# SRX.net
KiCad netlist of a schematic drawn in Altium Designer
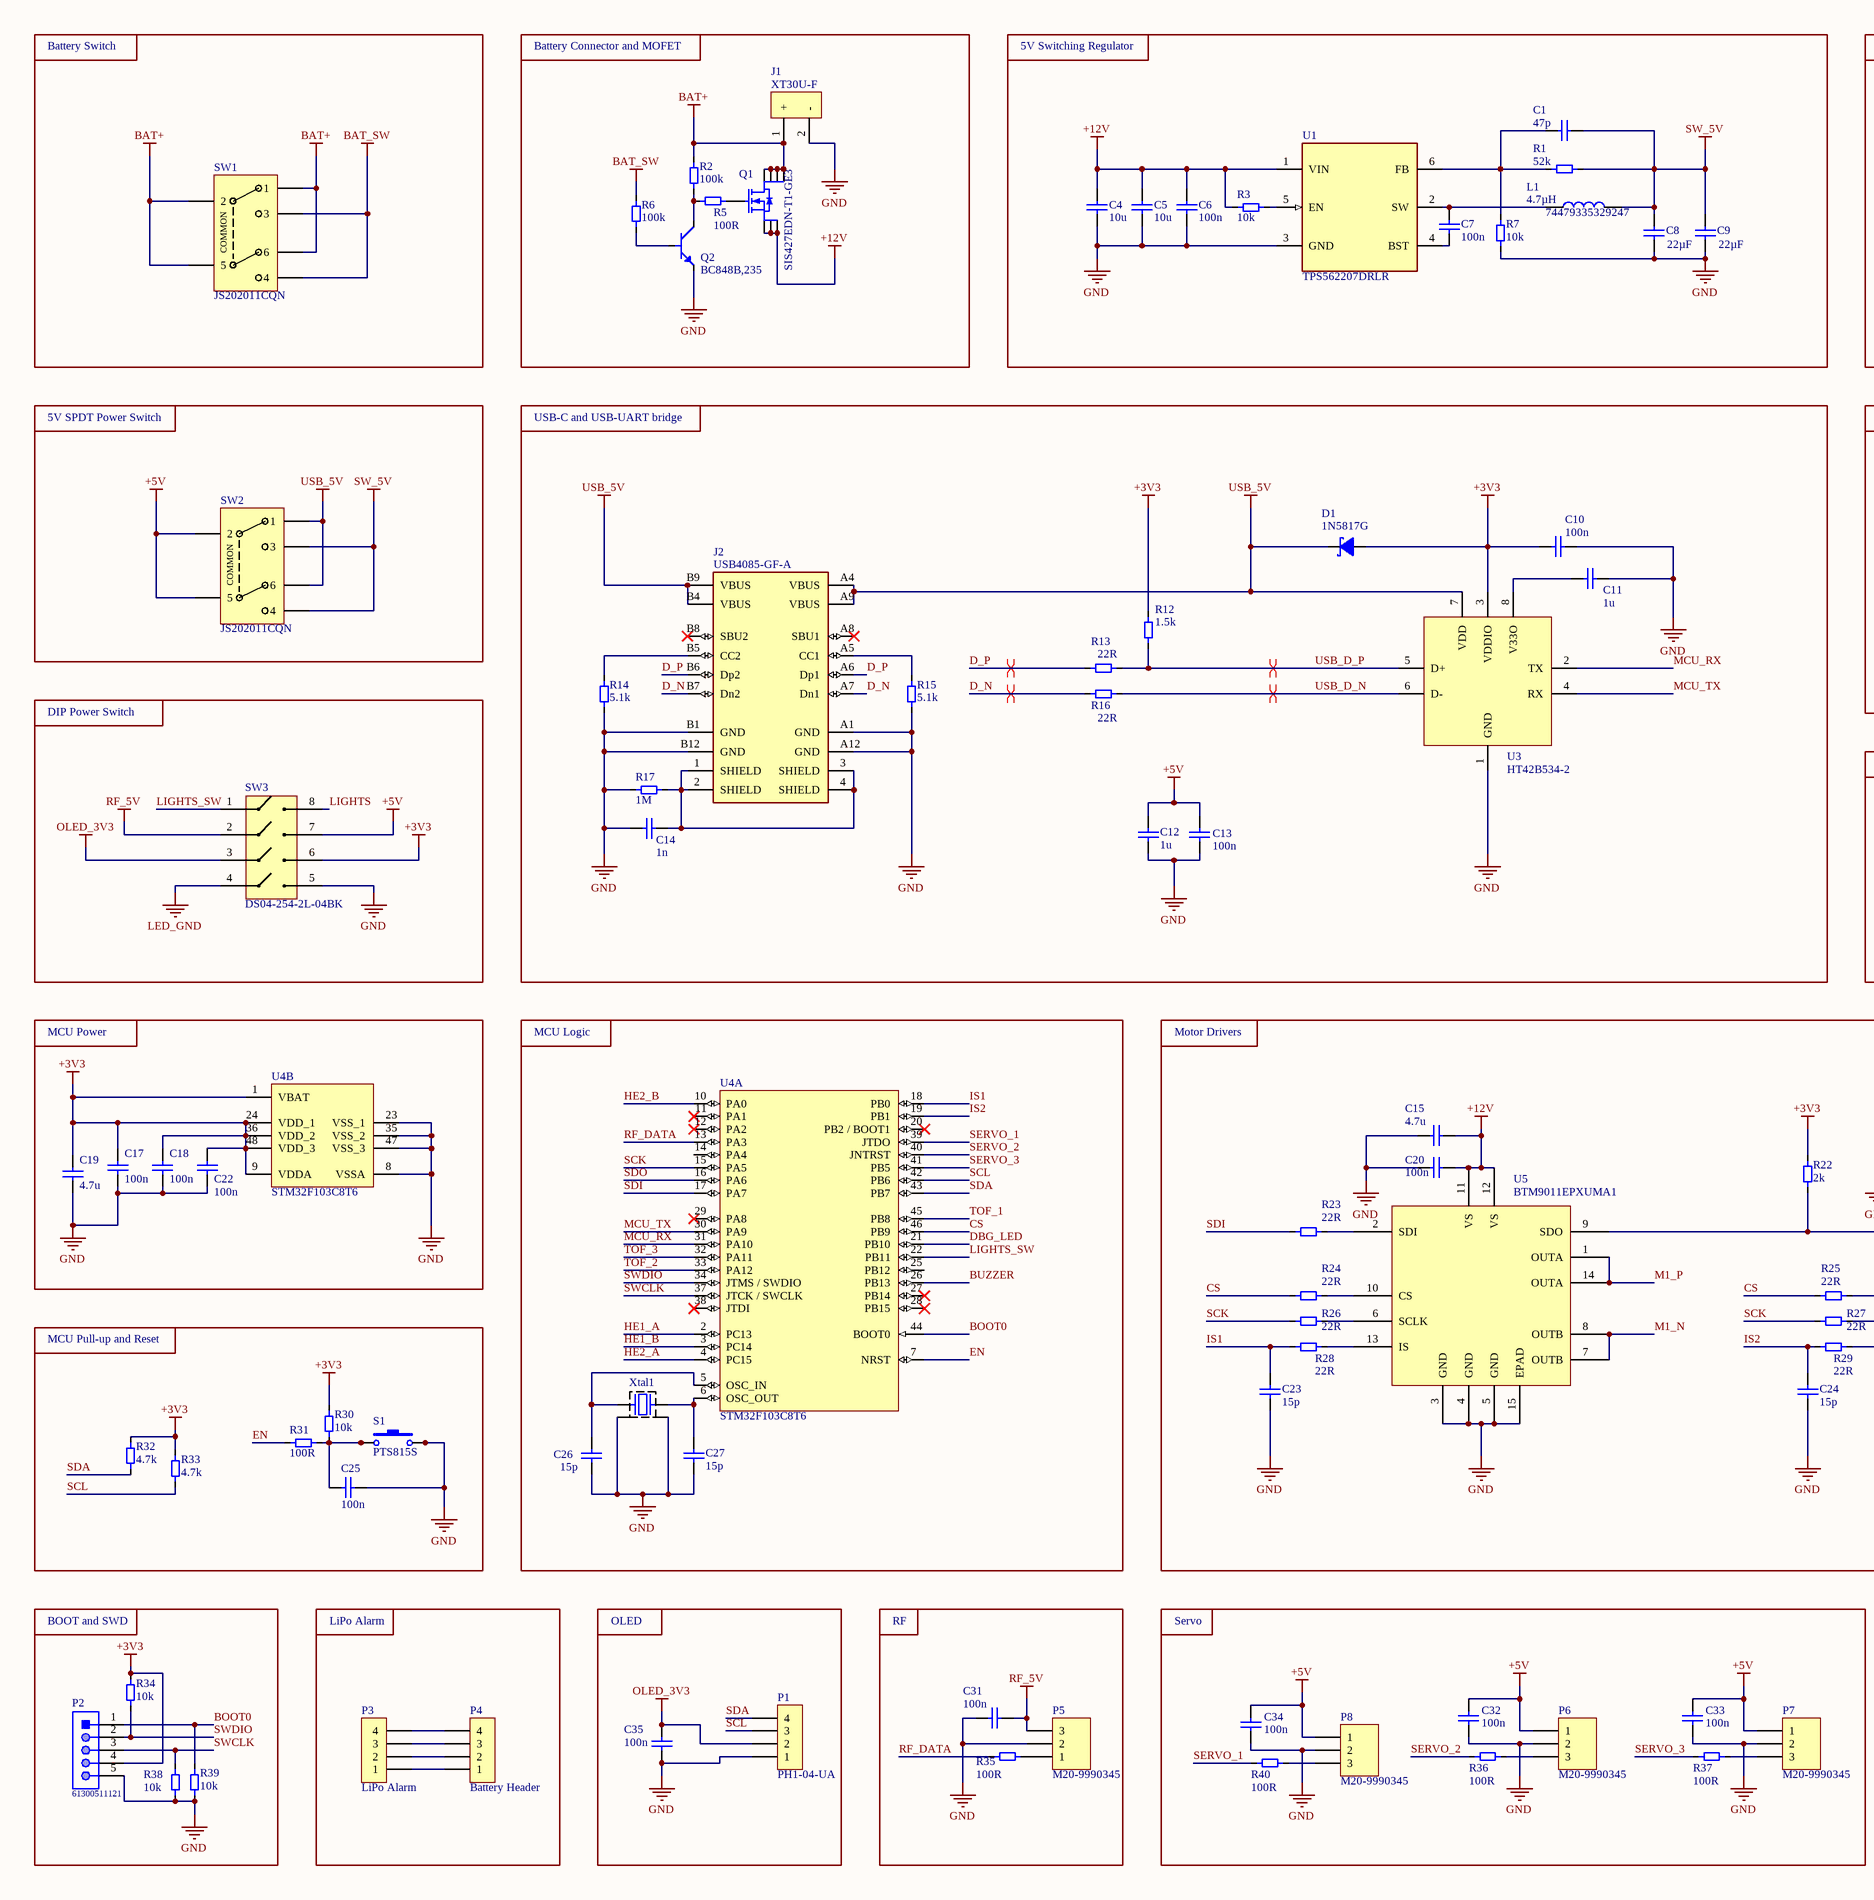
[diagram p0: SRX.SchDoc, left]
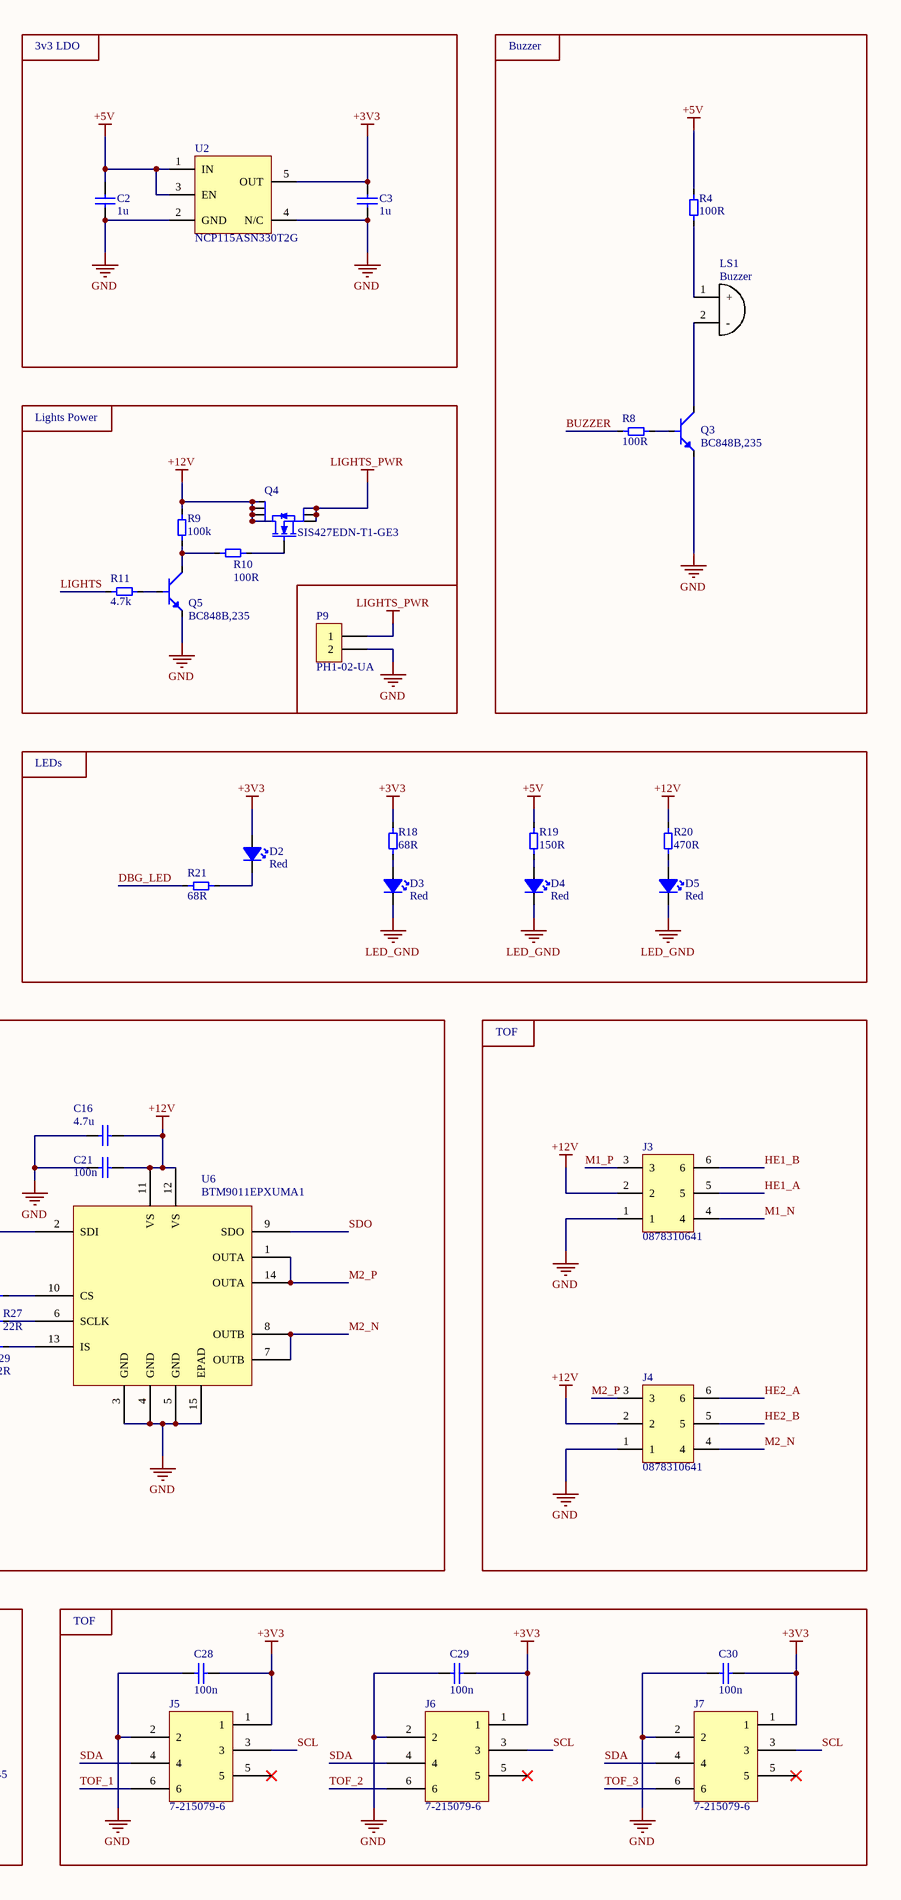
[diagram p1: SRX.SchDoc, right]

(export (version "E")
  (design (tool "Eeschema 10.0.6"))
  (components
    (comp (ref "C1")
      (value "47p")
      (footprint "MLCC_0603_M")
      (description "MLCC, 0603, 47p, 10%, 50V, X7R")
      (fields (field (name "MANUFACTURER") "Any") (field (name "TOLERANCE") "10%"))
      (libsource (lib "Krakul Vault") (part "CAPACITOR_NONPOL_IEC"))
    )
    (comp (ref "C2")
      (value "1u")
      (footprint "MLCC_0603_M")
      (description "MLCC, 0603, 1u, 10%, 50V, X5R")
      (fields (field (name "MANUFACTURER") "Any") (field (name "VOLTAGE") "50V"))
      (libsource (lib "Krakul Vault") (part "CAPACITOR_NONPOL_IEC"))
    )
    (comp (ref "C3")
      (value "1u")
      (footprint "MLCC_0603_M")
      (description "MLCC, 0603, 1u, 10%, 50V, X5R")
      (fields (field (name "MANUFACTURER") "Any") (field (name "VOLTAGE") "50V"))
      (libsource (lib "Krakul Vault") (part "CAPACITOR_NONPOL_IEC"))
    )
    (comp (ref "C4")
      (value "10u")
      (footprint "MLCC_0805_M")
      (description "MLCC, 0805, 10u, 10%, 50V, X5R")
      (fields (field (name "TOLERANCE") "10%") (field (name "VOLTAGE") "50V"))
      (libsource (lib "Krakul Vault") (part "CAPACITOR_NONPOL_IEC"))
    )
    (comp (ref "C5")
      (value "10u")
      (footprint "MLCC_0805_M")
      (description "MLCC, 0805, 10u, 10%, 50V, X5R")
      (fields (field (name "TOLERANCE") "10%") (field (name "VOLTAGE") "50V"))
      (libsource (lib "Krakul Vault") (part "CAPACITOR_NONPOL_IEC"))
    )
    (comp (ref "C6")
      (value "100n")
      (footprint "MLCC_0603_M")
      (description "MLCC, 0603, 100n, 10%, 50V, X7R")
      (fields (field (name "VOLTAGE") "50V") (field (name "TOLERANCE") "10%"))
      (libsource (lib "Krakul Vault") (part "CAPACITOR_NONPOL_IEC"))
    )
    (comp (ref "C7")
      (value "100n")
      (footprint "MLCC_0603_M")
      (description "MLCC, 0603, 100n, 10%, 50V, X7R")
      (fields (field (name "VOLTAGE") "50V") (field (name "TOLERANCE") "10%"))
      (libsource (lib "Krakul Vault") (part "CAPACITOR_NONPOL_IEC"))
    )
    (comp (ref "C8")
      (value "22µF")
      (footprint "1210_MLCC")
      (description "Capacitor;  Ceramic;  22uF;  Tol+10%;  SMT HighCapacitance;  16V;  X5R;  TR")
      (fields (field (name "TOLERANCE") "10%") (field (name "PART NUMBER") "Any"))
      (libsource (lib "Krakul Vault") (part "CAPACITOR_NONPOL_IEC"))
    )
    (comp (ref "C9")
      (value "22µF")
      (footprint "1210_MLCC")
      (description "Capacitor;  Ceramic;  22uF;  Tol+10%;  SMT HighCapacitance;  16V;  X5R;  TR")
      (fields (field (name "TOLERANCE") "10%") (field (name "PART NUMBER") "Any"))
      (libsource (lib "Krakul Vault") (part "CAPACITOR_NONPOL_IEC"))
    )
    (comp (ref "C10")
      (value "100n")
      (footprint "MLCC_0603_M")
      (description "MLCC, 0603, 100n, 10%, 50V, X7R")
      (fields (field (name "VOLTAGE") "50V") (field (name "TOLERANCE") "10%"))
      (libsource (lib "Krakul Vault") (part "CAPACITOR_NONPOL_IEC"))
    )
    (comp (ref "C11")
      (value "1u")
      (footprint "MLCC_0603_M")
      (description "MLCC, 0603, 1u, 10%, 50V, X5R")
      (fields (field (name "MANUFACTURER") "Any") (field (name "VOLTAGE") "50V"))
      (libsource (lib "Krakul Vault") (part "CAPACITOR_NONPOL_IEC"))
    )
    (comp (ref "C12")
      (value "1u")
      (footprint "MLCC_0603_M")
      (description "MLCC, 0603, 1u, 10%, 50V, X5R")
      (fields (field (name "MANUFACTURER") "Any") (field (name "VOLTAGE") "50V"))
      (libsource (lib "Krakul Vault") (part "CAPACITOR_NONPOL_IEC"))
    )
    (comp (ref "C13")
      (value "100n")
      (footprint "MLCC_0603_M")
      (description "MLCC, 0603, 100n, 10%, 50V, X7R")
      (fields (field (name "VOLTAGE") "50V") (field (name "TOLERANCE") "10%"))
      (libsource (lib "Krakul Vault") (part "CAPACITOR_NONPOL_IEC"))
    )
    (comp (ref "C14")
      (value "1n")
      (footprint "MLCC_0603_M")
      (description "MLCC, 0603, 1n, 10%, 50V, X5R")
      (fields (field (name "MANUFACTURER") "Any") (field (name "TOLERANCE") "10%"))
      (libsource (lib "Krakul Vault") (part "CAPACITOR_NONPOL_IEC"))
    )
    (comp (ref "C15")
      (value "4.7u")
      (footprint "MLCC_0603_M")
      (description "MLCC, 0603, 4.7u, 10%, 35V, X5R")
      (fields (field (name "TOLERANCE") "10%") (field (name "VOLTAGE") "35V"))
      (libsource (lib "Krakul Vault") (part "CAPACITOR_NONPOL_IEC"))
    )
    (comp (ref "C16")
      (value "4.7u")
      (footprint "MLCC_0603_M")
      (description "MLCC, 0603, 4.7u, 10%, 35V, X5R")
      (fields (field (name "TOLERANCE") "10%") (field (name "VOLTAGE") "35V"))
      (libsource (lib "Krakul Vault") (part "CAPACITOR_NONPOL_IEC"))
    )
    (comp (ref "C17")
      (value "100n")
      (footprint "MLCC_0603_M")
      (description "MLCC, 0603, 100n, 10%, 50V, X7R")
      (fields (field (name "VOLTAGE") "50V") (field (name "TOLERANCE") "10%"))
      (libsource (lib "Krakul Vault") (part "CAPACITOR_NONPOL_IEC"))
    )
    (comp (ref "C18")
      (value "100n")
      (footprint "MLCC_0603_M")
      (description "MLCC, 0603, 100n, 10%, 50V, X7R")
      (fields (field (name "VOLTAGE") "50V") (field (name "TOLERANCE") "10%"))
      (libsource (lib "Krakul Vault") (part "CAPACITOR_NONPOL_IEC"))
    )
    (comp (ref "C19")
      (value "4.7u")
      (footprint "MLCC_0805_M")
      (description "MLCC, 0805, 4.7u, 20%, 50V, X5R")
      (fields (field (name "MANUFACTURER") "Any") (field (name "VOLTAGE") "50V"))
      (libsource (lib "Krakul Vault") (part "CAPACITOR_NONPOL_IEC"))
    )
    (comp (ref "C20")
      (value "100n")
      (footprint "MLCC_0603_M")
      (description "MLCC, 0603, 100n, 10%, 35V, X7R")
      (fields (field (name "MANUFACTURER") "Any") (field (name "VOLTAGE") "35V"))
      (libsource (lib "Krakul Vault") (part "CAPACITOR_NONPOL_IEC"))
    )
    (comp (ref "C21")
      (value "100n")
      (footprint "MLCC_0603_M")
      (description "MLCC, 0603, 100n, 10%, 35V, X7R")
      (fields (field (name "MANUFACTURER") "Any") (field (name "VOLTAGE") "35V"))
      (libsource (lib "Krakul Vault") (part "CAPACITOR_NONPOL_IEC"))
    )
    (comp (ref "C22")
      (value "100n")
      (footprint "MLCC_0603_M")
      (description "MLCC, 0603, 100n, 10%, 50V, X7R")
      (fields (field (name "VOLTAGE") "50V") (field (name "TOLERANCE") "10%"))
      (libsource (lib "Krakul Vault") (part "CAPACITOR_NONPOL_IEC"))
    )
    (comp (ref "C23")
      (value "15p")
      (footprint "MLCC_0603_M")
      (description "MLCC, 0603, 15p, 5%, 50V, C0G/NP0")
      (fields (field (name "MANUFACTURER") "Any") (field (name "VOLTAGE") "50V"))
      (libsource (lib "Krakul Vault") (part "CAPACITOR_NONPOL_IEC"))
    )
    (comp (ref "C24")
      (value "15p")
      (footprint "MLCC_0603_M")
      (description "MLCC, 0603, 15p, 5%, 50V, C0G/NP0")
      (fields (field (name "MANUFACTURER") "Any") (field (name "VOLTAGE") "50V"))
      (libsource (lib "Krakul Vault") (part "CAPACITOR_NONPOL_IEC"))
    )
    (comp (ref "C25")
      (value "100n")
      (footprint "MLCC_0603_M")
      (description "MLCC, 0603, 100n, 10%, 50V, X7R")
      (fields (field (name "VOLTAGE") "50V") (field (name "TOLERANCE") "10%"))
      (libsource (lib "Krakul Vault") (part "CAPACITOR_NONPOL_IEC"))
    )
    (comp (ref "C26")
      (value "15p")
      (footprint "MLCC_0402_M")
      (description "MLCC, 0402, 15p, 10%, 25V, C0G/NP0")
      (fields (field (name "MANUFACTURER") "Any") (field (name "TOLERANCE") "10%"))
      (libsource (lib "Krakul Vault") (part "CAPACITOR_NONPOL_IEC"))
    )
    (comp (ref "C27")
      (value "15p")
      (footprint "MLCC_0402_M")
      (description "MLCC, 0402, 15p, 10%, 25V, C0G/NP0")
      (fields (field (name "MANUFACTURER") "Any") (field (name "TOLERANCE") "10%"))
      (libsource (lib "Krakul Vault") (part "CAPACITOR_NONPOL_IEC"))
    )
    (comp (ref "C28")
      (value "100n")
      (footprint "MLCC_0603_M")
      (description "MLCC, 0603, 100n, 10%, 50V, X7R")
      (fields (field (name "VOLTAGE") "50V") (field (name "TOLERANCE") "10%"))
      (libsource (lib "Krakul Vault") (part "CAPACITOR_NONPOL_IEC"))
    )
    (comp (ref "C29")
      (value "100n")
      (footprint "MLCC_0603_M")
      (description "MLCC, 0603, 100n, 10%, 50V, X7R")
      (fields (field (name "VOLTAGE") "50V") (field (name "TOLERANCE") "10%"))
      (libsource (lib "Krakul Vault") (part "CAPACITOR_NONPOL_IEC"))
    )
    (comp (ref "C30")
      (value "100n")
      (footprint "MLCC_0603_M")
      (description "MLCC, 0603, 100n, 10%, 50V, X7R")
      (fields (field (name "VOLTAGE") "50V") (field (name "TOLERANCE") "10%"))
      (libsource (lib "Krakul Vault") (part "CAPACITOR_NONPOL_IEC"))
    )
    (comp (ref "C31")
      (value "100n")
      (footprint "MLCC_0603_M")
      (description "MLCC, 0603, 100n, 10%, 50V, X7R")
      (fields (field (name "VOLTAGE") "50V") (field (name "TOLERANCE") "10%"))
      (libsource (lib "Krakul Vault") (part "CAPACITOR_NONPOL_IEC"))
    )
    (comp (ref "C32")
      (value "100n")
      (footprint "MLCC_0603_M")
      (description "MLCC, 0603, 100n, 10%, 50V, X7R")
      (fields (field (name "VOLTAGE") "50V") (field (name "TOLERANCE") "10%"))
      (libsource (lib "Krakul Vault") (part "CAPACITOR_NONPOL_IEC"))
    )
    (comp (ref "C33")
      (value "100n")
      (footprint "MLCC_0603_M")
      (description "MLCC, 0603, 100n, 10%, 50V, X7R")
      (fields (field (name "VOLTAGE") "50V") (field (name "TOLERANCE") "10%"))
      (libsource (lib "Krakul Vault") (part "CAPACITOR_NONPOL_IEC"))
    )
    (comp (ref "C34")
      (value "100n")
      (footprint "MLCC_0603_M")
      (description "MLCC, 0603, 100n, 10%, 50V, X7R")
      (fields (field (name "VOLTAGE") "50V") (field (name "TOLERANCE") "10%"))
      (libsource (lib "Krakul Vault") (part "CAPACITOR_NONPOL_IEC"))
    )
    (comp (ref "C35")
      (value "100n")
      (footprint "MLCC_0603_M")
      (description "MLCC, 0603, 100n, 10%, 50V, X7R")
      (fields (field (name "VOLTAGE") "50V") (field (name "TOLERANCE") "10%"))
      (libsource (lib "Krakul Vault") (part "CAPACITOR_NONPOL_IEC"))
    )
    (comp (ref "D1")
      (value "1N5817G")
      (footprint "SOD-323 based on 1N5817WS")
      (description "Rectifier Diode, Schottky, 1 Phase, 1 Element, 1A, 20V V(RRM), Silicon, DO-204AL")
      (fields (field (name "MANUFACTURER") "TWGMC / onsemi") (field (name "PART NUMBER") "1N5817WS"))
      (libsource (lib "Krakul Vault") (part "Schottky generic 2 pins"))
    )
    (comp (ref "D2")
      (value "Red")
      (footprint "0603 RED LED")
      (description "Generic red 0603 LED")
      (fields (field (name "PART NUMBER") "Any Red 0603 LED") (field (name "MANUFACTURER") "Any"))
      (libsource (lib "Krakul Vault") (part "LED generic"))
    )
    (comp (ref "D3")
      (value "Red")
      (footprint "0603 RED LED")
      (description "Generic red 0603 LED")
      (fields (field (name "PART NUMBER") "Any Red 0603 LED") (field (name "MANUFACTURER") "Any"))
      (libsource (lib "Krakul Vault") (part "LED generic"))
    )
    (comp (ref "D4")
      (value "Red")
      (footprint "0603 RED LED")
      (description "Generic red 0603 LED")
      (fields (field (name "PART NUMBER") "Any Red 0603 LED") (field (name "MANUFACTURER") "Any"))
      (libsource (lib "Krakul Vault") (part "LED generic"))
    )
    (comp (ref "D5")
      (value "Red")
      (footprint "0603 RED LED")
      (description "Generic red 0603 LED")
      (fields (field (name "PART NUMBER") "Any Red 0603 LED") (field (name "MANUFACTURER") "Any"))
      (libsource (lib "Krakul Vault") (part "LED generic"))
    )
    (comp (ref "J1")
      (value "XT30U-F")
      (footprint "XT30U-F")
      (description "Power Connector")
      (fields (field (name "MANUFACTURER") "AMASS"))
      (libsource (lib "Krakul Vault") (part "XT30U-F-Symbol-1"))
    )
    (comp (ref "J2")
      (value "USB4085-GF-A")
      (footprint "FP-USB4085-GF-A-MFG")
      (description "USB Connector, 16 Contact(s), Female, Right Angle, Solder Terminal, Locking, Receptacle")
      (fields (field (name "MANUFACTURER") "GCT") (field (name "PART NUMBER") "USB4800-03-A"))
      (libsource (lib "Krakul Vault") (part "USB4085-GF-A"))
    )
    (comp (ref "J3")
      (value "0878310641")
      (footprint "0878310641")
      (description "Conn Shrouded Header (2 Sides) HDR 6 POS 2mm Solder ST Top Entry Thru-Hole Milli-Grid Tube")
      (fields (field (name "MANUFACTURER") "Molex"))
      (libsource (lib "Krakul Vault") (part "0878310641"))
    )
    (comp (ref "J4")
      (value "0878310641")
      (footprint "0878310641")
      (description "Conn Shrouded Header (2 Sides) HDR 6 POS 2mm Solder ST Top Entry Thru-Hole Milli-Grid Tube")
      (fields (field (name "MANUFACTURER") "Molex"))
      (libsource (lib "Krakul Vault") (part "0878310641"))
    )
    (comp (ref "J5")
      (value "7-215079-6")
      (footprint "7-215079-6-Footprint-1")
      (description "Conn FFC Connector F 6 POS 1.27mm Solder ST Thru-Hole Automotive Box/Carton")
      (fields (field (name "MANUFACTURER") "TE Connectivity"))
      (libsource (lib "Krakul Vault") (part "7-215079-6"))
    )
    (comp (ref "J6")
      (value "7-215079-6")
      (footprint "7-215079-6-Footprint-1")
      (description "Conn FFC Connector F 6 POS 1.27mm Solder ST Thru-Hole Automotive Box/Carton")
      (fields (field (name "MANUFACTURER") "TE Connectivity"))
      (libsource (lib "Krakul Vault") (part "7-215079-6"))
    )
    (comp (ref "J7")
      (value "7-215079-6")
      (footprint "7-215079-6-Footprint-1")
      (description "Conn FFC Connector F 6 POS 1.27mm Solder ST Thru-Hole Automotive Box/Carton")
      (fields (field (name "MANUFACTURER") "TE Connectivity"))
      (libsource (lib "Krakul Vault") (part "7-215079-6"))
    )
    (comp (ref "L1")
      (value "74479335329247")
      (footprint "WE-PMFI_353220")
      (description "Power Inductor, 4.7Uh, 3.85A, Shielded Rohs Compliant: Yes")
      (fields (field (name "MANUFACTURER") "Wurth Elektronik") (field (name "ALTIUM_VALUE") "4.7µH"))
      (libsource (lib "Krakul Vault") (part "INDUCTOR_UNSHIELDED"))
    )
    (comp (ref "LS1")
      (value "Buzzer")
      (footprint "Buzzer-Footprint-1")
      (description "7mm")
      (fields (field (name "MANUFACTURER") "Unknown"))
      (libsource (lib "Krakul Vault") (part "Buzzer"))
    )
    (comp (ref "P1")
      (value "PH1-04-UA")
      (footprint "4Pos Pin Header Vertical")
      (description "4 POS 2.54mm Vertical THT Header")
      (fields (field (name "MANUFACTURER") "Adam Tech"))
      (libsource (lib "") (part "4POS GENERIC_1"))
    )
    (comp (ref "P2")
      (value "61300511121")
      (footprint "61300511121")
      (description "Conn Unshrouded Header HDR 5 POS 2.54mm Solder ST Top Entry Thru-Hole Bag")
      (fields (field (name "MANUFACTURER") "Wurth"))
      (libsource (lib "Krakul Vault") (part "WE-CN-1P-M-R5"))
    )
    (comp (ref "P3")
      (value "LiPo Alarm")
      (footprint "4Pos Pin Header Vertical")
      (description "4 POS 2.54mm Vertical THT Header")
      (fields (field (name "PART NUMBER") "PH1-04-UA") (field (name "MANUFACTURER") "Adam Tech"))
      (libsource (lib "Krakul Vault") (part "4POS GENERIC"))
    )
    (comp (ref "P4")
      (value "Battery Header")
      (footprint "4Pos Pin Header Vertical")
      (description "4 POS 2.54mm Vertical THT Header")
      (fields (field (name "PART NUMBER") "PH1-04-UA") (field (name "MANUFACTURER") "Adam Tech"))
      (libsource (lib "") (part "4POS GENERIC_1"))
    )
    (comp (ref "P5")
      (value "M20-9990345")
      (footprint "3Pos Pin Header")
      (description "Connector Header Through Hole 3 position 0.100\" (2.54mm)")
      (fields (field (name "MANUFACTURER") "Harwin Inc."))
      (libsource (lib "") (part "3 pin header_1"))
    )
    (comp (ref "P6")
      (value "M20-9990345")
      (footprint "3Pos Pin Header")
      (description "Connector Header Through Hole 3 position 0.100\" (2.54mm)")
      (fields (field (name "MANUFACTURER") "Harwin Inc."))
      (libsource (lib "Krakul Vault") (part "3 pin header"))
    )
    (comp (ref "P7")
      (value "M20-9990345")
      (footprint "3Pos Pin Header")
      (description "Connector Header Through Hole 3 position 0.100\" (2.54mm)")
      (fields (field (name "MANUFACTURER") "Harwin Inc."))
      (libsource (lib "Krakul Vault") (part "3 pin header"))
    )
    (comp (ref "P8")
      (value "M20-9990345")
      (footprint "3Pos Pin Header")
      (description "Connector Header Through Hole 3 position 0.100\" (2.54mm)")
      (fields (field (name "MANUFACTURER") "Harwin Inc."))
      (libsource (lib "Krakul Vault") (part "3 pin header"))
    )
    (comp (ref "P9")
      (value "PH1-02-UA")
      (footprint "2Pos Pin Header Vertical")
      (description "Conn Unshrouded Header HDR 2 POS 2.54mm Solder ST Top Entry Thru-Hole Bag")
      (fields (field (name "PART NUMBER") "PH1-04-UA") (field (name "MANUFACTURER") "Adam Tech"))
      (libsource (lib "Krakul Vault") (part "2POS GENERIC"))
    )
    (comp (ref "Q1")
      (value "SIS427EDN-T1-GE3")
      (footprint "Copy of TPN2R304PL,L1Q-Footprint-1")
      (description "Trans MOSFET P-CH 30V 15A 8-Pin PowerPAK EP T/R")
      (fields (field (name "MANUFACTURER") "Vishay Siliconix"))
      (libsource (lib "Krakul Vault") (part "P-CH MOSFET 8-pin v2"))
    )
    (comp (ref "Q2")
      (value "BC848B,235")
      (footprint "SOT-23-3")
      (description "Small Signal Bipolar Transistor, 0.1A I(C), 30V V(BR)CEO, 1-Element, NPN, Silicon, TO-236AB")
      (fields (field (name "MANUFACTURER") "Nexperia"))
      (libsource (lib "Krakul Vault") (part "NPN SOT23"))
    )
    (comp (ref "Q3")
      (value "BC848B,235")
      (footprint "SOT-23-3")
      (description "Small Signal Bipolar Transistor, 0.1A I(C), 30V V(BR)CEO, 1-Element, NPN, Silicon, TO-236AB")
      (fields (field (name "MANUFACTURER") "Nexperia"))
      (libsource (lib "Krakul Vault") (part "NPN SOT23"))
    )
    (comp (ref "Q4")
      (value "SIS427EDN-T1-GE3")
      (footprint "Copy of TPN2R304PL,L1Q-Footprint-1")
      (description "Trans MOSFET P-CH 30V 15A 8-Pin PowerPAK EP T/R")
      (fields (field (name "MANUFACTURER") "Vishay Siliconix"))
      (libsource (lib "Krakul Vault") (part "P-CH MOSFET 8-pin v2"))
    )
    (comp (ref "Q5")
      (value "BC848B,235")
      (footprint "SOT-23-3")
      (description "Small Signal Bipolar Transistor, 0.1A I(C), 30V V(BR)CEO, 1-Element, NPN, Silicon, TO-236AB")
      (fields (field (name "MANUFACTURER") "Nexperia"))
      (libsource (lib "Krakul Vault") (part "NPN SOT23"))
    )
    (comp (ref "R1")
      (value "52k")
      (footprint "Resistor_0603_M")
      (description "Resistor, 0603, 53.6k, 1%, 1/10W")
      (fields (field (name "MANUFACTURER") "Any") (field (name "TOLERANCE") "1%"))
      (libsource (lib "Krakul Vault") (part "RESISTOR_GENERIC_IEC"))
    )
    (comp (ref "R2")
      (value "100k")
      (footprint "Resistor_0603_M")
      (description "Resistor, 0603, 100k, 1%, 1/10W")
      (fields (field (name "TOLERANCE") "1%") (field (name "MANUFACTURER") "Any"))
      (libsource (lib "Krakul Vault") (part "RESISTOR_GENERIC_IEC"))
    )
    (comp (ref "R3")
      (value "10k")
      (footprint "Resistor_0603_M")
      (description "Resistor, 0603, 10k, 1%, 1/10W")
      (fields (field (name "MANUFACTURER") "Any") (field (name "TOLERANCE") "1%"))
      (libsource (lib "Krakul Vault") (part "RESISTOR_GENERIC_IEC"))
    )
    (comp (ref "R4")
      (value "100R")
      (footprint "Resistor_0603_M")
      (description "Resistor, 0603, 100R, 1%, 1/10W")
      (fields (field (name "POWER") "100mW") (field (name "MANUFACTURER") "Any"))
      (libsource (lib "Krakul Vault") (part "RESISTOR_GENERIC_IEC"))
    )
    (comp (ref "R5")
      (value "100R")
      (footprint "Resistor_0603_M")
      (description "Resistor, 0603, 100R, 1%, 1/10W")
      (fields (field (name "POWER") "100mW") (field (name "MANUFACTURER") "Any"))
      (libsource (lib "Krakul Vault") (part "RESISTOR_GENERIC_IEC"))
    )
    (comp (ref "R6")
      (value "100k")
      (footprint "Resistor_0603_M")
      (description "Resistor, 0603, 100k, 1%, 1/10W")
      (fields (field (name "TOLERANCE") "1%") (field (name "MANUFACTURER") "Any"))
      (libsource (lib "Krakul Vault") (part "RESISTOR_GENERIC_IEC"))
    )
    (comp (ref "R7")
      (value "10k")
      (footprint "Resistor_0603_M")
      (description "Resistor, 0603, 10k, 1%, 1/10W")
      (fields (field (name "MANUFACTURER") "Any") (field (name "TOLERANCE") "1%"))
      (libsource (lib "Krakul Vault") (part "RESISTOR_GENERIC_IEC"))
    )
    (comp (ref "R8")
      (value "100R")
      (footprint "Resistor_0603_M")
      (description "Resistor, 0603, 100R, 1%, 1/10W")
      (fields (field (name "POWER") "100mW") (field (name "MANUFACTURER") "Any"))
      (libsource (lib "Krakul Vault") (part "RESISTOR_GENERIC_IEC"))
    )
    (comp (ref "R9")
      (value "100k")
      (footprint "Resistor_0603_M")
      (description "Resistor, 0603, 100k, 1%, 1/10W")
      (fields (field (name "TOLERANCE") "1%") (field (name "MANUFACTURER") "Any"))
      (libsource (lib "Krakul Vault") (part "RESISTOR_GENERIC_IEC"))
    )
    (comp (ref "R10")
      (value "100R")
      (footprint "Resistor_0603_M")
      (description "Resistor, 0603, 100R, 1%, 1/10W")
      (fields (field (name "POWER") "100mW") (field (name "MANUFACTURER") "Any"))
      (libsource (lib "Krakul Vault") (part "RESISTOR_GENERIC_IEC"))
    )
    (comp (ref "R11")
      (value "4.7k")
      (footprint "Resistor_0603_M")
      (description "Resistor, 0603, 4.7k, 1%, 1/10W")
      (fields (field (name "MANUFACTURER") "Any") (field (name "POWER") "100mW"))
      (libsource (lib "Krakul Vault") (part "RESISTOR_GENERIC_IEC"))
    )
    (comp (ref "R12")
      (value "1.5k")
      (footprint "Resistor_0603_M")
      (description "Resistor, 0603, 1.5k, 1%, 1/10W")
      (fields (field (name "MANUFACTURER") "Any") (field (name "POWER") "100mW"))
      (libsource (lib "Krakul Vault") (part "RESISTOR_GENERIC_IEC"))
    )
    (comp (ref "R13")
      (value "22R")
      (footprint "Resistor_0603_M")
      (description "Resistor, 0603, 22R, 1%, 1/10W")
      (fields (field (name "TOLERANCE") "1%") (field (name "MANUFACTURER") "Any"))
      (libsource (lib "Krakul Vault") (part "RESISTOR_GENERIC_IEC"))
    )
    (comp (ref "R14")
      (value "5.1k")
      (footprint "Resistor_0603_M")
      (description "Resistor, 0603, 5.1k, 1%, 1/10W")
      (fields (field (name "POWER") "100mW") (field (name "MANUFACTURER") "Any"))
      (libsource (lib "Krakul Vault") (part "RESISTOR_GENERIC_IEC"))
    )
    (comp (ref "R15")
      (value "5.1k")
      (footprint "Resistor_0603_M")
      (description "Resistor, 0603, 5.1k, 1%, 1/10W")
      (fields (field (name "POWER") "100mW") (field (name "MANUFACTURER") "Any"))
      (libsource (lib "Krakul Vault") (part "RESISTOR_GENERIC_IEC"))
    )
    (comp (ref "R16")
      (value "22R")
      (footprint "Resistor_0603_M")
      (description "Resistor, 0603, 22R, 1%, 1/10W")
      (fields (field (name "TOLERANCE") "1%") (field (name "MANUFACTURER") "Any"))
      (libsource (lib "Krakul Vault") (part "RESISTOR_GENERIC_IEC"))
    )
    (comp (ref "R17")
      (value "1M")
      (footprint "Resistor_1206_M")
      (description "Resistor, 1206, 1M, 1%, 1/4W")
      (fields (field (name "MANUFACTURER") "Any"))
      (libsource (lib "Krakul Vault") (part "RESISTOR_GENERIC_IEC"))
    )
    (comp (ref "R18")
      (value "68R")
      (footprint "Resistor_0603_M")
      (description "Resistor, 0603, 100R, ≤5%, ≥1/16W")
      (fields (field (name "MANUFACTURER") "Any"))
      (libsource (lib "Krakul Vault") (part "RESISTOR_GENERIC_IEC"))
    )
    (comp (ref "R19")
      (value "150R")
      (footprint "Resistor_0603_M")
      (description "Resistor, 0603, 200R, 1%, 1/10W")
      (fields (field (name "TOLERANCE") "1%") (field (name "POWER") "100mW"))
      (libsource (lib "Krakul Vault") (part "RESISTOR_GENERIC_IEC"))
    )
    (comp (ref "R20")
      (value "470R")
      (footprint "Resistor_0603_M")
      (description "Resistor, 0603, 680R, 1%, 1/10W")
      (fields (field (name "POWER") "100mW") (field (name "TOLERANCE") "1%"))
      (libsource (lib "Krakul Vault") (part "RESISTOR_GENERIC_IEC"))
    )
    (comp (ref "R21")
      (value "68R")
      (footprint "Resistor_0603_M")
      (description "Resistor, 0603, 200R, 1%, 1/10W")
      (fields (field (name "TOLERANCE") "1%") (field (name "POWER") "100mW"))
      (libsource (lib "Krakul Vault") (part "RESISTOR_GENERIC_IEC"))
    )
    (comp (ref "R22")
      (value "2k")
      (footprint "Resistor_0603_M")
      (description "Resistor, 0603, 2k, 1%, 1/10W")
      (fields (field (name "MANUFACTURER") "Any") (field (name "POWER") "100mW"))
      (libsource (lib "Krakul Vault") (part "RESISTOR_GENERIC_IEC"))
    )
    (comp (ref "R23")
      (value "22R")
      (footprint "Resistor_0603_M")
      (description "Resistor, 0603, 22R, 1%, 1/10W")
      (fields (field (name "TOLERANCE") "1%") (field (name "MANUFACTURER") "Any"))
      (libsource (lib "Krakul Vault") (part "RESISTOR_GENERIC_IEC"))
    )
    (comp (ref "R24")
      (value "22R")
      (footprint "Resistor_0603_M")
      (description "Resistor, 0603, 22R, 1%, 1/10W")
      (fields (field (name "TOLERANCE") "1%") (field (name "MANUFACTURER") "Any"))
      (libsource (lib "Krakul Vault") (part "RESISTOR_GENERIC_IEC"))
    )
    (comp (ref "R25")
      (value "22R")
      (footprint "Resistor_0603_M")
      (description "Resistor, 0603, 22R, 1%, 1/10W")
      (fields (field (name "TOLERANCE") "1%") (field (name "MANUFACTURER") "Any"))
      (libsource (lib "Krakul Vault") (part "RESISTOR_GENERIC_IEC"))
    )
    (comp (ref "R26")
      (value "22R")
      (footprint "Resistor_0603_M")
      (description "Resistor, 0603, 22R, 1%, 1/10W")
      (fields (field (name "TOLERANCE") "1%") (field (name "MANUFACTURER") "Any"))
      (libsource (lib "Krakul Vault") (part "RESISTOR_GENERIC_IEC"))
    )
    (comp (ref "R27")
      (value "22R")
      (footprint "Resistor_0603_M")
      (description "Resistor, 0603, 22R, 1%, 1/10W")
      (fields (field (name "TOLERANCE") "1%") (field (name "MANUFACTURER") "Any"))
      (libsource (lib "Krakul Vault") (part "RESISTOR_GENERIC_IEC"))
    )
    (comp (ref "R28")
      (value "22R")
      (footprint "Resistor_0603_M")
      (description "Resistor, 0603, 22R, 1%, 1/10W")
      (fields (field (name "TOLERANCE") "1%") (field (name "MANUFACTURER") "Any"))
      (libsource (lib "Krakul Vault") (part "RESISTOR_GENERIC_IEC"))
    )
    (comp (ref "R29")
      (value "22R")
      (footprint "Resistor_0603_M")
      (description "Resistor, 0603, 22R, 1%, 1/10W")
      (fields (field (name "TOLERANCE") "1%") (field (name "MANUFACTURER") "Any"))
      (libsource (lib "Krakul Vault") (part "RESISTOR_GENERIC_IEC"))
    )
    (comp (ref "R30")
      (value "10k")
      (footprint "Resistor_0603_M")
      (description "Resistor, 0603, 10k, 1%, 1/10W")
      (fields (field (name "MANUFACTURER") "Any") (field (name "TOLERANCE") "1%"))
      (libsource (lib "Krakul Vault") (part "RESISTOR_GENERIC_IEC"))
    )
    (comp (ref "R31")
      (value "100R")
      (footprint "Resistor_0603_M")
      (description "Resistor, 0603, 100R, 1%, 1/10W")
      (fields (field (name "POWER") "100mW") (field (name "MANUFACTURER") "Any"))
      (libsource (lib "Krakul Vault") (part "RESISTOR_GENERIC_IEC"))
    )
    (comp (ref "R32")
      (value "4.7k")
      (footprint "Resistor_0603_M")
      (description "Resistor, 0603, 4.7k, 1%, 1/10W")
      (fields (field (name "MANUFACTURER") "Any") (field (name "POWER") "100mW"))
      (libsource (lib "Krakul Vault") (part "RESISTOR_GENERIC_IEC"))
    )
    (comp (ref "R33")
      (value "4.7k")
      (footprint "Resistor_0603_M")
      (description "Resistor, 0603, 4.7k, 1%, 1/10W")
      (fields (field (name "MANUFACTURER") "Any") (field (name "POWER") "100mW"))
      (libsource (lib "Krakul Vault") (part "RESISTOR_GENERIC_IEC"))
    )
    (comp (ref "R34")
      (value "10k")
      (footprint "Resistor_0603_M")
      (description "Resistor, 0603, 10k, 1%, 1/10W")
      (fields (field (name "MANUFACTURER") "Any") (field (name "TOLERANCE") "1%"))
      (libsource (lib "Krakul Vault") (part "RESISTOR_GENERIC_IEC"))
    )
    (comp (ref "R35")
      (value "100R")
      (footprint "Resistor_0603_M")
      (description "Resistor, 0603, 100R, 1%, 1/10W")
      (fields (field (name "POWER") "100mW") (field (name "MANUFACTURER") "Any"))
      (libsource (lib "Krakul Vault") (part "RESISTOR_GENERIC_IEC"))
    )
    (comp (ref "R36")
      (value "100R")
      (footprint "Resistor_0603_M")
      (description "Resistor, 0603, 100R, 1%, 1/10W")
      (fields (field (name "POWER") "100mW") (field (name "MANUFACTURER") "Any"))
      (libsource (lib "Krakul Vault") (part "RESISTOR_GENERIC_IEC"))
    )
    (comp (ref "R37")
      (value "100R")
      (footprint "Resistor_0603_M")
      (description "Resistor, 0603, 100R, 1%, 1/10W")
      (fields (field (name "POWER") "100mW") (field (name "MANUFACTURER") "Any"))
      (libsource (lib "Krakul Vault") (part "RESISTOR_GENERIC_IEC"))
    )
    (comp (ref "R38")
      (value "10k")
      (footprint "Resistor_0603_M")
      (description "Resistor, 0603, 10k, 1%, 1/10W")
      (fields (field (name "MANUFACTURER") "Any") (field (name "TOLERANCE") "1%"))
      (libsource (lib "Krakul Vault") (part "RESISTOR_GENERIC_IEC"))
    )
    (comp (ref "R39")
      (value "10k")
      (footprint "Resistor_0603_M")
      (description "Resistor, 0603, 10k, ≤5%, ≥1/16W")
      (fields (field (name "MANUFACTURER") "Any"))
      (libsource (lib "Krakul Vault") (part "RESISTOR_GENERIC_IEC"))
    )
    (comp (ref "R40")
      (value "100R")
      (footprint "Resistor_0603_M")
      (description "Resistor, 0603, 100R, 1%, 1/10W")
      (fields (field (name "POWER") "100mW") (field (name "MANUFACTURER") "Any"))
      (libsource (lib "Krakul Vault") (part "RESISTOR_GENERIC_IEC"))
    )
    (comp (ref "S1")
      (value "PTS815S")
      (footprint "PTS815 SJM 250 SMTR LFS")
      (description "Tactile Switches SWITCH TACTILE")
      (fields (field (name "MANUFACTURER") "C&K") (field (name "PART NUMBER") "PTS815 SJM 250 SMTR LFS"))
      (libsource (lib "Krakul Vault") (part "PTS815SJM250SMTRLFS"))
    )
    (comp (ref "SW1")
      (value "JS202011CQN")
      (footprint "FP-JS202011CQN-MFG")
      (description "Slide Switch, 1 Positions, Dpdt, Latched, 0.3A, 6Vdc, 6 Pcb Hole Cnt, Solder Terminal, Through")
      (fields (field (name "MANUFACTURER") "C&K"))
      (libsource (lib "Krakul Vault") (part "JS202011CQN-Symbol-1"))
    )
    (comp (ref "SW2")
      (value "JS202011CQN")
      (footprint "FP-JS202011CQN-MFG")
      (description "Slide Switch, 1 Positions, Dpdt, Latched, 0.3A, 6Vdc, 6 Pcb Hole Cnt, Solder Terminal, Through")
      (fields (field (name "MANUFACTURER") "C&K"))
      (libsource (lib "Krakul Vault") (part "JS202011CQN-Symbol-1"))
    )
    (comp (ref "SW3")
      (value "DS04-254-2L-04BK")
      (footprint "DS04-254-2L-04BK-Footprint-1")
      (description "Switch DIP OFF ON SPST 4 Flat Slide 0.025A 24VDC PC Pins 2.54mm Thru-Hole Tube")
      (fields (field (name "MANUFACTURER") "Same Sky"))
      (libsource (lib "Krakul Vault") (part "4 DIP switch"))
    )
    (comp (ref "U1")
      (value "TPS562207DRLR")
      (footprint "FP-DRL0006A-MFG")
      (description "4.3-V to 17-V input, 2-A synchronous buck converter in SOT563 6-SOT-5X3 -40 to 125")
      (fields (field (name "MANUFACTURER") "Texas Instruments"))
      (libsource (lib "Krakul Vault") (part "TPS562207DRLR"))
    )
    (comp (ref "U2")
      (value "NCP115ASN330T2G")
      (footprint "TSOP-5")
      (fields (field (name "MANUFACTURER") "onsemi"))
      (libsource (lib "Krakul Vault") (part "NCP115ASN330T2G"))
    )
    (comp (ref "U3")
      (value "HT42B534-2")
      (footprint "SOP-8 150mil")
      (description "USB to UART 3Mbps USB 2.0 SOP-8 Interface Controllers RoHS")
      (fields (field (name "MANUFACTURER") "HOLTEK"))
      (libsource (lib "Krakul Vault") (part "HT42B534-2"))
    )
    (comp (ref "U4")
      (value "STM32F103C8T6")
      (footprint "STM-LQFP48_M")
      (description "MCU 32-bit STM32F1 ARM Cortex M3 RISC 64KB Flash 2.5V/3.3V 48-Pin LQFP Tray")
      (fields (field (name "MANUFACTURER") "STMicroelectronics"))
      (libsource (lib "Krakul Vault") (part "MC-ARM-STM32F103X4_6-SQ48"))
    )
    (comp (ref "U5")
      (value "BTM9011EPXUMA1")
      (footprint "BTM9011EPXUMA1")
      (description "DC Mtr Drive, Brush, 150DEGC, TSSOPEP-14 Rohs Compliant: Yes")
      (fields (field (name "MANUFACTURER") "Infineon Technologies"))
      (libsource (lib "Krakul Vault") (part "BTM9011EPXUMA1"))
    )
    (comp (ref "U6")
      (value "BTM9011EPXUMA1")
      (footprint "BTM9011EPXUMA1")
      (description "DC Mtr Drive, Brush, 150DEGC, TSSOPEP-14 Rohs Compliant: Yes")
      (fields (field (name "MANUFACTURER") "Infineon Technologies"))
      (libsource (lib "Krakul Vault") (part "BTM9011EPXUMA1"))
    )
    (comp (ref "Xtal1")
      (value "ABM11-16.000MHZ-12-N1G-T")
      (footprint "FP-ABM11-MFG")
      (description "Crystal 16MHz ±10ppm (Tol) ±15ppm (Stability) 12pF FUND 150Ohm 4-Pin Ultra Mini-CSMD T/R")
      (fields (field (name "MANUFACTURER") "Abracon LLC") (field (name "TOLERANCE") "0.001%"))
      (libsource (lib "Krakul Vault") (part "Crystal 4 pins"))
    )
  )
  (nets
    (net (code "1") (name "+3V3") (class "Default")
      (node (ref "C10") (pin "1") (pinfunction "1_1") (pintype "passive"))
      (node (ref "C17") (pin "1") (pinfunction "1_1") (pintype "passive"))
      (node (ref "C18") (pin "1") (pinfunction "1_1") (pintype "passive"))
      (node (ref "C19") (pin "2") (pinfunction "2_2") (pintype "passive"))
      (node (ref "C22") (pin "1") (pinfunction "1_1") (pintype "passive"))
      (node (ref "C28") (pin "1") (pinfunction "1_1") (pintype "passive"))
      (node (ref "C29") (pin "1") (pinfunction "1_1") (pintype "passive"))
      (node (ref "C3") (pin "2") (pinfunction "2_2") (pintype "passive"))
      (node (ref "C30") (pin "1") (pinfunction "1_1") (pintype "passive"))
      (node (ref "D1") (pin "2") (pinfunction "A_2") (pintype "passive"))
      (node (ref "D2") (pin "2") (pinfunction "A_2") (pintype "passive"))
      (node (ref "J5") (pin "1") (pinfunction "1_1") (pintype "passive"))
      (node (ref "J6") (pin "1") (pinfunction "1_1") (pintype "passive"))
      (node (ref "J7") (pin "1") (pinfunction "1_1") (pintype "passive"))
      (node (ref "P2") (pin "4") (pinfunction "4_4") (pintype "passive"))
      (node (ref "R12") (pin "2") (pinfunction "2_2") (pintype "passive"))
      (node (ref "R18") (pin "2") (pinfunction "2_2") (pintype "passive"))
      (node (ref "R22") (pin "2") (pinfunction "2_2") (pintype "passive"))
      (node (ref "R30") (pin "2") (pinfunction "2_2") (pintype "passive"))
      (node (ref "R32") (pin "2") (pinfunction "2_2") (pintype "passive"))
      (node (ref "R33") (pin "2") (pinfunction "2_2") (pintype "passive"))
      (node (ref "R34") (pin "1") (pinfunction "1_1") (pintype "passive"))
      (node (ref "SW3") (pin "6") (pinfunction "6_6") (pintype "passive"))
      (node (ref "U2") (pin "5") (pinfunction "OUT_5") (pintype "passive"))
      (node (ref "U3") (pin "3") (pinfunction "VDDIO_3") (pintype "passive"))
      (node (ref "U4") (pin "1") (pinfunction "VBAT_1") (pintype "power_in"))
      (node (ref "U4") (pin "24") (pinfunction "VDD_1_24") (pintype "power_in"))
      (node (ref "U4") (pin "36") (pinfunction "VDD_2_36") (pintype "power_in"))
      (node (ref "U4") (pin "48") (pinfunction "VDD_3_48") (pintype "power_in"))
      (node (ref "U4") (pin "9") (pinfunction "VDDA_9") (pintype "power_in"))
    )
    (net (code "2") (name "+5V") (class "Default")
      (node (ref "C12") (pin "2") (pinfunction "2_2") (pintype "passive"))
      (node (ref "C13") (pin "1") (pinfunction "1_1") (pintype "passive"))
      (node (ref "C2") (pin "2") (pinfunction "2_2") (pintype "passive"))
      (node (ref "C32") (pin "1") (pinfunction "1_1") (pintype "passive"))
      (node (ref "C33") (pin "1") (pinfunction "1_1") (pintype "passive"))
      (node (ref "C34") (pin "1") (pinfunction "1_1") (pintype "passive"))
      (node (ref "P6") (pin "1") (pinfunction "1_1") (pintype "passive"))
      (node (ref "P7") (pin "1") (pinfunction "1_1") (pintype "passive"))
      (node (ref "P8") (pin "1") (pinfunction "1_1") (pintype "passive"))
      (node (ref "R19") (pin "1") (pinfunction "1_1") (pintype "passive"))
      (node (ref "R4") (pin "1") (pinfunction "1_1") (pintype "passive"))
      (node (ref "SW2") (pin "2") (pinfunction "2_2") (pintype "passive"))
      (node (ref "SW2") (pin "5") (pinfunction "5_5") (pintype "passive"))
      (node (ref "SW3") (pin "7") (pinfunction "7_7") (pintype "passive"))
      (node (ref "U2") (pin "1") (pinfunction "IN_1") (pintype "passive"))
      (node (ref "U2") (pin "3") (pinfunction "EN_3") (pintype "passive"))
    )
    (net (code "3") (name "+12V") (class "Default")
      (node (ref "C15") (pin "2") (pinfunction "2_2") (pintype "passive"))
      (node (ref "C16") (pin "2") (pinfunction "2_2") (pintype "passive"))
      (node (ref "C20") (pin "2") (pinfunction "2_2") (pintype "passive"))
      (node (ref "C21") (pin "2") (pinfunction "2_2") (pintype "passive"))
      (node (ref "C4") (pin "2") (pinfunction "2_2") (pintype "passive"))
      (node (ref "C5") (pin "2") (pinfunction "2_2") (pintype "passive"))
      (node (ref "C6") (pin "2") (pinfunction "2_2") (pintype "passive"))
      (node (ref "J3") (pin "2") (pinfunction "2_2") (pintype "passive"))
      (node (ref "J4") (pin "2") (pinfunction "2_2") (pintype "passive"))
      (node (ref "Q1") (pin "1") (pinfunction "S_1") (pintype "passive"))
      (node (ref "Q1") (pin "2") (pinfunction "S_2") (pintype "passive"))
      (node (ref "Q1") (pin "3") (pinfunction "S_3") (pintype "passive"))
      (node (ref "Q4") (pin "5") (pinfunction "D_5") (pintype "passive"))
      (node (ref "Q4") (pin "6") (pinfunction "D_6") (pintype "passive"))
      (node (ref "Q4") (pin "7") (pinfunction "D_7") (pintype "passive"))
      (node (ref "Q4") (pin "8") (pinfunction "D_8") (pintype "passive"))
      (node (ref "R20") (pin "2") (pinfunction "2_2") (pintype "passive"))
      (node (ref "R3") (pin "1") (pinfunction "1_1") (pintype "passive"))
      (node (ref "R9") (pin "2") (pinfunction "2_2") (pintype "passive"))
      (node (ref "U1") (pin "1") (pinfunction "VIN_1") (pintype "power_in"))
      (node (ref "U5") (pin "11") (pinfunction "VS_11") (pintype "passive"))
      (node (ref "U5") (pin "12") (pinfunction "VS_12") (pintype "passive"))
      (node (ref "U6") (pin "11") (pinfunction "VS_11") (pintype "passive"))
      (node (ref "U6") (pin "12") (pinfunction "VS_12") (pintype "passive"))
    )
    (net (code "4") (name "/BOOT0") (class "Default")
      (node (ref "P2") (pin "1") (pinfunction "1_1") (pintype "passive"))
      (node (ref "R39") (pin "2") (pinfunction "2_2") (pintype "passive"))
      (node (ref "U4") (pin "44") (pinfunction "BOOT0_44") (pintype "input"))
    )
    (net (code "5") (name "/BUZZER") (class "Default")
      (node (ref "R8") (pin "1") (pinfunction "1_1") (pintype "passive"))
      (node (ref "U4") (pin "26") (pinfunction "PB13_26") (pintype "bidirectional"))
    )
    (net (code "6") (name "/CS") (class "Default")
      (node (ref "R24") (pin "1") (pinfunction "1_1") (pintype "passive"))
      (node (ref "R25") (pin "1") (pinfunction "1_1") (pintype "passive"))
      (node (ref "U4") (pin "46") (pinfunction "PB9_46") (pintype "bidirectional"))
    )
    (net (code "7") (name "/DBG_LED") (class "Default")
      (node (ref "R21") (pin "2") (pinfunction "2_2") (pintype "passive"))
      (node (ref "U4") (pin "21") (pinfunction "PB10_21") (pintype "bidirectional"))
    )
    (net (code "8") (name "/D_N") (class "Default")
      (node (ref "J2") (pin "A7") (pinfunction "Dn1_A7") (pintype "bidirectional"))
      (node (ref "J2") (pin "B7") (pinfunction "Dn2_B7") (pintype "bidirectional"))
      (node (ref "R16") (pin "1") (pinfunction "1_1") (pintype "passive"))
    )
    (net (code "9") (name "/D_P") (class "Default")
      (node (ref "J2") (pin "A6") (pinfunction "Dp1_A6") (pintype "bidirectional"))
      (node (ref "J2") (pin "B6") (pinfunction "Dp2_B6") (pintype "bidirectional"))
      (node (ref "R13") (pin "1") (pinfunction "1_1") (pintype "passive"))
    )
    (net (code "10") (name "/EN") (class "Default")
      (node (ref "R31") (pin "2") (pinfunction "2_2") (pintype "passive"))
      (node (ref "U4") (pin "7") (pinfunction "NRST_7") (pintype "bidirectional"))
    )
    (net (code "11") (name "/HE1_A") (class "Default")
      (node (ref "J3") (pin "5") (pinfunction "5_5") (pintype "passive"))
      (node (ref "U4") (pin "2") (pinfunction "PC13_2") (pintype "bidirectional"))
    )
    (net (code "12") (name "/HE1_B") (class "Default")
      (node (ref "J3") (pin "6") (pinfunction "6_6") (pintype "passive"))
      (node (ref "U4") (pin "3") (pinfunction "PC14_3") (pintype "bidirectional"))
    )
    (net (code "13") (name "/HE2_A") (class "Default")
      (node (ref "J4") (pin "6") (pinfunction "6_6") (pintype "passive"))
      (node (ref "U4") (pin "4") (pinfunction "PC15_4") (pintype "bidirectional"))
    )
    (net (code "14") (name "/HE2_B") (class "Default")
      (node (ref "J4") (pin "5") (pinfunction "5_5") (pintype "passive"))
      (node (ref "U4") (pin "10") (pinfunction "PA0_10") (pintype "bidirectional"))
    )
    (net (code "15") (name "/IS1") (class "Default")
      (node (ref "C23") (pin "1") (pinfunction "1_1") (pintype "passive"))
      (node (ref "R28") (pin "1") (pinfunction "1_1") (pintype "passive"))
      (node (ref "U4") (pin "18") (pinfunction "PB0_18") (pintype "bidirectional"))
    )
    (net (code "16") (name "/IS2") (class "Default")
      (node (ref "C24") (pin "1") (pinfunction "1_1") (pintype "passive"))
      (node (ref "R29") (pin "1") (pinfunction "1_1") (pintype "passive"))
      (node (ref "U4") (pin "19") (pinfunction "PB1_19") (pintype "bidirectional"))
    )
    (net (code "17") (name "/LIGHTS") (class "Default")
      (node (ref "R11") (pin "2") (pinfunction "2_2") (pintype "passive"))
      (node (ref "SW3") (pin "8") (pinfunction "8_8") (pintype "passive"))
    )
    (net (code "18") (name "/LIGHTS_SW") (class "Default")
      (node (ref "SW3") (pin "1") (pinfunction "1_1") (pintype "passive"))
      (node (ref "U4") (pin "22") (pinfunction "PB11_22") (pintype "bidirectional"))
    )
    (net (code "19") (name "/M1_N") (class "Default")
      (node (ref "J3") (pin "4") (pinfunction "4_4") (pintype "passive"))
      (node (ref "U5") (pin "7") (pinfunction "OUTB_7") (pintype "passive"))
      (node (ref "U5") (pin "8") (pinfunction "OUTB_8") (pintype "passive"))
    )
    (net (code "20") (name "/M1_P") (class "Default")
      (node (ref "J3") (pin "3") (pinfunction "3_3") (pintype "passive"))
      (node (ref "U5") (pin "1") (pinfunction "OUTA_1") (pintype "passive"))
      (node (ref "U5") (pin "14") (pinfunction "OUTA_14") (pintype "passive"))
    )
    (net (code "21") (name "/M2_N") (class "Default")
      (node (ref "J4") (pin "4") (pinfunction "4_4") (pintype "passive"))
      (node (ref "U6") (pin "7") (pinfunction "OUTB_7") (pintype "passive"))
      (node (ref "U6") (pin "8") (pinfunction "OUTB_8") (pintype "passive"))
    )
    (net (code "22") (name "/M2_P") (class "Default")
      (node (ref "J4") (pin "3") (pinfunction "3_3") (pintype "passive"))
      (node (ref "U6") (pin "1") (pinfunction "OUTA_1") (pintype "passive"))
      (node (ref "U6") (pin "14") (pinfunction "OUTA_14") (pintype "passive"))
    )
    (net (code "23") (name "/MCU_RX") (class "Default")
      (node (ref "U3") (pin "2") (pinfunction "TX_2") (pintype "passive"))
      (node (ref "U4") (pin "31") (pinfunction "PA10_31") (pintype "bidirectional"))
    )
    (net (code "24") (name "/MCU_TX") (class "Default")
      (node (ref "U3") (pin "4") (pinfunction "RX_4") (pintype "passive"))
      (node (ref "U4") (pin "30") (pinfunction "PA9_30") (pintype "bidirectional"))
    )
    (net (code "25") (name "/RF_DATA") (class "Default")
      (node (ref "R35") (pin "1") (pinfunction "1_1") (pintype "passive"))
      (node (ref "U4") (pin "13") (pinfunction "PA3_13") (pintype "bidirectional"))
    )
    (net (code "26") (name "/SCK") (class "Default")
      (node (ref "R26") (pin "1") (pinfunction "1_1") (pintype "passive"))
      (node (ref "R27") (pin "1") (pinfunction "1_1") (pintype "passive"))
      (node (ref "U4") (pin "15") (pinfunction "PA5_15") (pintype "bidirectional"))
    )
    (net (code "27") (name "/SCL") (class "Default")
      (node (ref "J5") (pin "3") (pinfunction "3_3") (pintype "passive"))
      (node (ref "J6") (pin "3") (pinfunction "3_3") (pintype "passive"))
      (node (ref "J7") (pin "3") (pinfunction "3_3") (pintype "passive"))
      (node (ref "P1") (pin "3") (pinfunction "3_3") (pintype "passive"))
      (node (ref "R33") (pin "1") (pinfunction "1_1") (pintype "passive"))
      (node (ref "U4") (pin "42") (pinfunction "PB6_42") (pintype "bidirectional"))
    )
    (net (code "28") (name "/SDA") (class "Default")
      (node (ref "J5") (pin "4") (pinfunction "4_4") (pintype "passive"))
      (node (ref "J6") (pin "4") (pinfunction "4_4") (pintype "passive"))
      (node (ref "J7") (pin "4") (pinfunction "4_4") (pintype "passive"))
      (node (ref "P1") (pin "4") (pinfunction "4_4") (pintype "passive"))
      (node (ref "R32") (pin "1") (pinfunction "1_1") (pintype "passive"))
      (node (ref "U4") (pin "43") (pinfunction "PB7_43") (pintype "bidirectional"))
    )
    (net (code "29") (name "/SDI") (class "Default")
      (node (ref "R23") (pin "1") (pinfunction "1_1") (pintype "passive"))
      (node (ref "U4") (pin "17") (pinfunction "PA7_17") (pintype "bidirectional"))
    )
    (net (code "30") (name "/SDO") (class "Default")
      (node (ref "U4") (pin "16") (pinfunction "PA6_16") (pintype "bidirectional"))
      (node (ref "U6") (pin "9") (pinfunction "SDO_9") (pintype "passive"))
    )
    (net (code "31") (name "/SERVO_1") (class "Default")
      (node (ref "R40") (pin "2") (pinfunction "2_2") (pintype "passive"))
      (node (ref "U4") (pin "39") (pinfunction "JTDO_39") (pintype "bidirectional"))
    )
    (net (code "32") (name "/SERVO_2") (class "Default")
      (node (ref "R36") (pin "2") (pinfunction "2_2") (pintype "passive"))
      (node (ref "U4") (pin "40") (pinfunction "JNTRST_40") (pintype "bidirectional"))
    )
    (net (code "33") (name "/SERVO_3") (class "Default")
      (node (ref "R37") (pin "2") (pinfunction "2_2") (pintype "passive"))
      (node (ref "U4") (pin "41") (pinfunction "PB5_41") (pintype "bidirectional"))
    )
    (net (code "34") (name "/SWCLK") (class "Default")
      (node (ref "P2") (pin "3") (pinfunction "3_3") (pintype "passive"))
      (node (ref "R38") (pin "2") (pinfunction "2_2") (pintype "passive"))
      (node (ref "U4") (pin "37") (pinfunction "JTCK_/_SWCLK_37") (pintype "bidirectional"))
    )
    (net (code "35") (name "/SWDIO") (class "Default")
      (node (ref "P2") (pin "2") (pinfunction "2_2") (pintype "passive"))
      (node (ref "R34") (pin "2") (pinfunction "2_2") (pintype "passive"))
      (node (ref "U4") (pin "34") (pinfunction "JTMS_/_SWDIO_34") (pintype "bidirectional"))
    )
    (net (code "36") (name "/TOF_1") (class "Default")
      (node (ref "J5") (pin "6") (pinfunction "6_6") (pintype "passive"))
      (node (ref "U4") (pin "45") (pinfunction "PB8_45") (pintype "bidirectional"))
    )
    (net (code "37") (name "/TOF_2") (class "Default")
      (node (ref "J6") (pin "6") (pinfunction "6_6") (pintype "passive"))
      (node (ref "U4") (pin "33") (pinfunction "PA12_33") (pintype "bidirectional"))
    )
    (net (code "38") (name "/TOF_3") (class "Default")
      (node (ref "J7") (pin "6") (pinfunction "6_6") (pintype "passive"))
      (node (ref "U4") (pin "32") (pinfunction "PA11_32") (pintype "bidirectional"))
    )
    (net (code "39") (name "/USB_D_N") (class "Default")
      (node (ref "R16") (pin "2") (pinfunction "2_2") (pintype "passive"))
      (node (ref "U3") (pin "6") (pinfunction "D-_6") (pintype "passive"))
    )
    (net (code "40") (name "/USB_D_P") (class "Default")
      (node (ref "R12") (pin "1") (pinfunction "1_1") (pintype "passive"))
      (node (ref "R13") (pin "2") (pinfunction "2_2") (pintype "passive"))
      (node (ref "U3") (pin "5") (pinfunction "D+_5") (pintype "passive"))
    )
    (net (code "41") (name "BAT+") (class "Default")
      (node (ref "J1") (pin "1") (pinfunction "+_1") (pintype "passive"))
      (node (ref "Q1") (pin "5") (pinfunction "D_5") (pintype "passive"))
      (node (ref "Q1") (pin "6") (pinfunction "D_6") (pintype "passive"))
      (node (ref "Q1") (pin "7") (pinfunction "D_7") (pintype "passive"))
      (node (ref "Q1") (pin "8") (pinfunction "D_8") (pintype "passive"))
      (node (ref "R2") (pin "2") (pinfunction "2_2") (pintype "passive"))
      (node (ref "SW1") (pin "1") (pinfunction "1_1") (pintype "passive"))
      (node (ref "SW1") (pin "2") (pinfunction "2_2") (pintype "passive"))
      (node (ref "SW1") (pin "5") (pinfunction "5_5") (pintype "passive"))
      (node (ref "SW1") (pin "6") (pinfunction "6_6") (pintype "passive"))
    )
    (net (code "42") (name "BAT_SW") (class "Default")
      (node (ref "R6") (pin "2") (pinfunction "2_2") (pintype "passive"))
      (node (ref "SW1") (pin "3") (pinfunction "3_3") (pintype "passive"))
      (node (ref "SW1") (pin "4") (pinfunction "4_4") (pintype "passive"))
    )
    (net (code "43") (name "GND") (class "Default")
      (node (ref "C10") (pin "2") (pinfunction "2_2") (pintype "passive"))
      (node (ref "C11") (pin "2") (pinfunction "2_2") (pintype "passive"))
      (node (ref "C12") (pin "1") (pinfunction "1_1") (pintype "passive"))
      (node (ref "C13") (pin "2") (pinfunction "2_2") (pintype "passive"))
      (node (ref "C14") (pin "1") (pinfunction "1_1") (pintype "passive"))
      (node (ref "C15") (pin "1") (pinfunction "1_1") (pintype "passive"))
      (node (ref "C16") (pin "1") (pinfunction "1_1") (pintype "passive"))
      (node (ref "C17") (pin "2") (pinfunction "2_2") (pintype "passive"))
      (node (ref "C18") (pin "2") (pinfunction "2_2") (pintype "passive"))
      (node (ref "C19") (pin "1") (pinfunction "1_1") (pintype "passive"))
      (node (ref "C2") (pin "1") (pinfunction "1_1") (pintype "passive"))
      (node (ref "C20") (pin "1") (pinfunction "1_1") (pintype "passive"))
      (node (ref "C21") (pin "1") (pinfunction "1_1") (pintype "passive"))
      (node (ref "C22") (pin "2") (pinfunction "2_2") (pintype "passive"))
      (node (ref "C23") (pin "2") (pinfunction "2_2") (pintype "passive"))
      (node (ref "C24") (pin "2") (pinfunction "2_2") (pintype "passive"))
      (node (ref "C25") (pin "1") (pinfunction "1_1") (pintype "passive"))
      (node (ref "C26") (pin "1") (pinfunction "1_1") (pintype "passive"))
      (node (ref "C27") (pin "1") (pinfunction "1_1") (pintype "passive"))
      (node (ref "C28") (pin "2") (pinfunction "2_2") (pintype "passive"))
      (node (ref "C29") (pin "2") (pinfunction "2_2") (pintype "passive"))
      (node (ref "C3") (pin "1") (pinfunction "1_1") (pintype "passive"))
      (node (ref "C30") (pin "2") (pinfunction "2_2") (pintype "passive"))
      (node (ref "C31") (pin "2") (pinfunction "2_2") (pintype "passive"))
      (node (ref "C32") (pin "2") (pinfunction "2_2") (pintype "passive"))
      (node (ref "C33") (pin "2") (pinfunction "2_2") (pintype "passive"))
      (node (ref "C34") (pin "2") (pinfunction "2_2") (pintype "passive"))
      (node (ref "C35") (pin "2") (pinfunction "2_2") (pintype "passive"))
      (node (ref "C4") (pin "1") (pinfunction "1_1") (pintype "passive"))
      (node (ref "C5") (pin "1") (pinfunction "1_1") (pintype "passive"))
      (node (ref "C6") (pin "1") (pinfunction "1_1") (pintype "passive"))
      (node (ref "C8") (pin "1") (pinfunction "1_1") (pintype "passive"))
      (node (ref "C9") (pin "1") (pinfunction "1_1") (pintype "passive"))
      (node (ref "J1") (pin "2") (pinfunction "-_2") (pintype "passive"))
      (node (ref "J2") (pin "A1") (pinfunction "GND_A1") (pintype "power_in"))
      (node (ref "J2") (pin "A12") (pinfunction "GND_A12") (pintype "power_in"))
      (node (ref "J2") (pin "B1") (pinfunction "GND_B1") (pintype "power_in"))
      (node (ref "J2") (pin "B12") (pinfunction "GND_B12") (pintype "power_in"))
      (node (ref "J3") (pin "1") (pinfunction "1_1") (pintype "passive"))
      (node (ref "J4") (pin "1") (pinfunction "1_1") (pintype "passive"))
      (node (ref "J5") (pin "2") (pinfunction "2_2") (pintype "passive"))
      (node (ref "J6") (pin "2") (pinfunction "2_2") (pintype "passive"))
      (node (ref "J7") (pin "2") (pinfunction "2_2") (pintype "passive"))
      (node (ref "P1") (pin "1") (pinfunction "1_1") (pintype "passive"))
      (node (ref "P2") (pin "5") (pinfunction "5_5") (pintype "passive"))
      (node (ref "P5") (pin "2") (pinfunction "2_2") (pintype "passive"))
      (node (ref "P6") (pin "2") (pinfunction "2_2") (pintype "passive"))
      (node (ref "P7") (pin "2") (pinfunction "2_2") (pintype "passive"))
      (node (ref "P8") (pin "2") (pinfunction "2_2") (pintype "passive"))
      (node (ref "P9") (pin "2") (pinfunction "2_2") (pintype "passive"))
      (node (ref "Q2") (pin "2") (pinfunction "E_2") (pintype "power_in"))
      (node (ref "Q3") (pin "2") (pinfunction "E_2") (pintype "power_in"))
      (node (ref "Q5") (pin "2") (pinfunction "E_2") (pintype "power_in"))
      (node (ref "R14") (pin "1") (pinfunction "1_1") (pintype "passive"))
      (node (ref "R15") (pin "2") (pinfunction "2_2") (pintype "passive"))
      (node (ref "R17") (pin "2") (pinfunction "2_2") (pintype "passive"))
      (node (ref "R38") (pin "1") (pinfunction "1_1") (pintype "passive"))
      (node (ref "R39") (pin "1") (pinfunction "1_1") (pintype "passive"))
      (node (ref "R7") (pin "1") (pinfunction "1_1") (pintype "passive"))
      (node (ref "S1") (pin "3") (pinfunction "3_3") (pintype "passive"))
      (node (ref "S1") (pin "4") (pinfunction "4_4") (pintype "passive"))
      (node (ref "SW3") (pin "5") (pinfunction "5_5") (pintype "passive"))
      (node (ref "U1") (pin "3") (pinfunction "GND_3") (pintype "power_in"))
      (node (ref "U2") (pin "2") (pinfunction "GND_2") (pintype "passive"))
      (node (ref "U2") (pin "4") (pinfunction "N/C_4") (pintype "passive"))
      (node (ref "U3") (pin "1") (pinfunction "GND_1") (pintype "passive"))
      (node (ref "U4") (pin "23") (pinfunction "VSS_1_23") (pintype "power_in"))
      (node (ref "U4") (pin "35") (pinfunction "VSS_2_35") (pintype "power_in"))
      (node (ref "U4") (pin "47") (pinfunction "VSS_3_47") (pintype "power_in"))
      (node (ref "U4") (pin "8") (pinfunction "VSSA_8") (pintype "power_in"))
      (node (ref "U5") (pin "15") (pinfunction "EPAD_15") (pintype "passive"))
      (node (ref "U5") (pin "3") (pinfunction "GND_3") (pintype "passive"))
      (node (ref "U5") (pin "4") (pinfunction "GND_4") (pintype "passive"))
      (node (ref "U5") (pin "5") (pinfunction "GND_5") (pintype "passive"))
      (node (ref "U6") (pin "15") (pinfunction "EPAD_15") (pintype "passive"))
      (node (ref "U6") (pin "3") (pinfunction "GND_3") (pintype "passive"))
      (node (ref "U6") (pin "4") (pinfunction "GND_4") (pintype "passive"))
      (node (ref "U6") (pin "5") (pinfunction "GND_5") (pintype "passive"))
      (node (ref "Xtal1") (pin "2") (pinfunction "2_2") (pintype "power_in"))
      (node (ref "Xtal1") (pin "4") (pinfunction "4_4") (pintype "power_in"))
    )
    (net (code "44") (name "LED_GND") (class "Default")
      (node (ref "D3") (pin "1") (pinfunction "C_1") (pintype "passive"))
      (node (ref "D4") (pin "1") (pinfunction "C_1") (pintype "passive"))
      (node (ref "D5") (pin "1") (pinfunction "C_1") (pintype "passive"))
      (node (ref "SW3") (pin "4") (pinfunction "4_4") (pintype "passive"))
    )
    (net (code "45") (name "LIGHTS_PWR") (class "Default")
      (node (ref "P9") (pin "1") (pinfunction "1_1") (pintype "passive"))
      (node (ref "Q4") (pin "1") (pinfunction "S_1") (pintype "passive"))
      (node (ref "Q4") (pin "2") (pinfunction "S_2") (pintype "passive"))
      (node (ref "Q4") (pin "3") (pinfunction "S_3") (pintype "passive"))
    )
    (net (code "46") (name "Net-(C14-Pad2)") (class "Default")
      (node (ref "C14") (pin "2") (pinfunction "2_2") (pintype "passive"))
      (node (ref "J2") (pin "1") (pinfunction "SHIELD_1") (pintype "passive"))
      (node (ref "J2") (pin "2") (pinfunction "SHIELD_2") (pintype "passive"))
      (node (ref "J2") (pin "3") (pinfunction "SHIELD_3") (pintype "passive"))
      (node (ref "J2") (pin "4") (pinfunction "SHIELD_4") (pintype "passive"))
      (node (ref "R17") (pin "1") (pinfunction "1_1") (pintype "passive"))
    )
    (net (code "47") (name "Net-(C25-Pad2)") (class "Default")
      (node (ref "C25") (pin "2") (pinfunction "2_2") (pintype "passive"))
      (node (ref "R30") (pin "1") (pinfunction "1_1") (pintype "passive"))
      (node (ref "R31") (pin "1") (pinfunction "1_1") (pintype "passive"))
      (node (ref "S1") (pin "1") (pinfunction "1_1") (pintype "passive"))
      (node (ref "S1") (pin "2") (pinfunction "2_2") (pintype "passive"))
    )
    (net (code "48") (name "Net-(D2-C)") (class "Default")
      (node (ref "D2") (pin "1") (pinfunction "C_1") (pintype "passive"))
      (node (ref "R21") (pin "1") (pinfunction "1_1") (pintype "passive"))
    )
    (net (code "49") (name "Net-(D3-A)") (class "Default")
      (node (ref "D3") (pin "2") (pinfunction "A_2") (pintype "passive"))
      (node (ref "R18") (pin "1") (pinfunction "1_1") (pintype "passive"))
    )
    (net (code "50") (name "Net-(D4-A)") (class "Default")
      (node (ref "D4") (pin "2") (pinfunction "A_2") (pintype "passive"))
      (node (ref "R19") (pin "2") (pinfunction "2_2") (pintype "passive"))
    )
    (net (code "51") (name "Net-(D5-A)") (class "Default")
      (node (ref "D5") (pin "2") (pinfunction "A_2") (pintype "passive"))
      (node (ref "R20") (pin "1") (pinfunction "1_1") (pintype "passive"))
    )
    (net (code "52") (name "Net-(J2-CC1)") (class "Default")
      (node (ref "J2") (pin "A5") (pinfunction "CC1_A5") (pintype "bidirectional"))
      (node (ref "R15") (pin "1") (pinfunction "1_1") (pintype "passive"))
    )
    (net (code "53") (name "Net-(J2-CC2)") (class "Default")
      (node (ref "J2") (pin "B5") (pinfunction "CC2_B5") (pintype "bidirectional"))
      (node (ref "R14") (pin "2") (pinfunction "2_2") (pintype "passive"))
    )
    (net (code "54") (name "Net-(LS1-+)") (class "Default")
      (node (ref "LS1") (pin "1") (pinfunction "+_1") (pintype "passive"))
      (node (ref "R4") (pin "2") (pinfunction "2_2") (pintype "passive"))
    )
    (net (code "55") (name "Net-(LS1--)") (class "Default")
      (node (ref "LS1") (pin "2") (pinfunction "-_2") (pintype "passive"))
      (node (ref "Q3") (pin "3") (pinfunction "C_3") (pintype "power_in"))
    )
    (net (code "56") (name "Net-(P3-Pad1)") (class "Default")
      (node (ref "P3") (pin "1") (pinfunction "1_1") (pintype "passive"))
      (node (ref "P4") (pin "1") (pinfunction "1_1") (pintype "passive"))
    )
    (net (code "57") (name "Net-(P3-Pad2)") (class "Default")
      (node (ref "P3") (pin "2") (pinfunction "2_2") (pintype "passive"))
      (node (ref "P4") (pin "2") (pinfunction "2_2") (pintype "passive"))
    )
    (net (code "58") (name "Net-(P3-Pad3)") (class "Default")
      (node (ref "P3") (pin "3") (pinfunction "3_3") (pintype "passive"))
      (node (ref "P4") (pin "3") (pinfunction "3_3") (pintype "passive"))
    )
    (net (code "59") (name "Net-(P3-Pad4)") (class "Default")
      (node (ref "P3") (pin "4") (pinfunction "4_4") (pintype "passive"))
      (node (ref "P4") (pin "4") (pinfunction "4_4") (pintype "passive"))
    )
    (net (code "60") (name "Net-(P5-Pad1)") (class "Default")
      (node (ref "P5") (pin "1") (pinfunction "1_1") (pintype "passive"))
      (node (ref "R35") (pin "2") (pinfunction "2_2") (pintype "passive"))
    )
    (net (code "61") (name "Net-(P6-Pad3)") (class "Default")
      (node (ref "P6") (pin "3") (pinfunction "3_3") (pintype "passive"))
      (node (ref "R36") (pin "1") (pinfunction "1_1") (pintype "passive"))
    )
    (net (code "62") (name "Net-(P7-Pad3)") (class "Default")
      (node (ref "P7") (pin "3") (pinfunction "3_3") (pintype "passive"))
      (node (ref "R37") (pin "1") (pinfunction "1_1") (pintype "passive"))
    )
    (net (code "63") (name "Net-(P8-Pad3)") (class "Default")
      (node (ref "P8") (pin "3") (pinfunction "3_3") (pintype "passive"))
      (node (ref "R40") (pin "1") (pinfunction "1_1") (pintype "passive"))
    )
    (net (code "64") (name "Net-(Q1-G)") (class "Default")
      (node (ref "Q1") (pin "4") (pinfunction "G_4") (pintype "passive"))
      (node (ref "R5") (pin "1") (pinfunction "1_1") (pintype "passive"))
    )
    (net (code "65") (name "Net-(Q2-B)") (class "Default")
      (node (ref "Q2") (pin "1") (pinfunction "B_1") (pintype "power_in"))
      (node (ref "R6") (pin "1") (pinfunction "1_1") (pintype "passive"))
    )
    (net (code "66") (name "Net-(Q2-C)") (class "Default")
      (node (ref "Q2") (pin "3") (pinfunction "C_3") (pintype "power_in"))
      (node (ref "R2") (pin "1") (pinfunction "1_1") (pintype "passive"))
      (node (ref "R5") (pin "2") (pinfunction "2_2") (pintype "passive"))
    )
    (net (code "67") (name "Net-(Q3-B)") (class "Default")
      (node (ref "Q3") (pin "1") (pinfunction "B_1") (pintype "power_in"))
      (node (ref "R8") (pin "2") (pinfunction "2_2") (pintype "passive"))
    )
    (net (code "68") (name "Net-(Q4-G)") (class "Default")
      (node (ref "Q4") (pin "4") (pinfunction "G_4") (pintype "passive"))
      (node (ref "R10") (pin "1") (pinfunction "1_1") (pintype "passive"))
    )
    (net (code "69") (name "Net-(Q5-B)") (class "Default")
      (node (ref "Q5") (pin "1") (pinfunction "B_1") (pintype "power_in"))
      (node (ref "R11") (pin "1") (pinfunction "1_1") (pintype "passive"))
    )
    (net (code "70") (name "Net-(Q5-C)") (class "Default")
      (node (ref "Q5") (pin "3") (pinfunction "C_3") (pintype "power_in"))
      (node (ref "R10") (pin "2") (pinfunction "2_2") (pintype "passive"))
      (node (ref "R9") (pin "1") (pinfunction "1_1") (pintype "passive"))
    )
    (net (code "71") (name "Net-(U1-BST)") (class "Default")
      (node (ref "C7") (pin "1") (pinfunction "1_1") (pintype "passive"))
      (node (ref "U1") (pin "4") (pinfunction "BST_4") (pintype "passive"))
    )
    (net (code "72") (name "Net-(U1-EN)") (class "Default")
      (node (ref "R3") (pin "2") (pinfunction "2_2") (pintype "passive"))
      (node (ref "U1") (pin "5") (pinfunction "EN_5") (pintype "input"))
    )
    (net (code "73") (name "Net-(U1-FB)") (class "Default")
      (node (ref "C1") (pin "1") (pinfunction "1_1") (pintype "passive"))
      (node (ref "R1") (pin "1") (pinfunction "1_1") (pintype "passive"))
      (node (ref "R7") (pin "2") (pinfunction "2_2") (pintype "passive"))
      (node (ref "U1") (pin "6") (pinfunction "FB_6") (pintype "passive"))
    )
    (net (code "74") (name "Net-(U1-SW)") (class "Default")
      (node (ref "C7") (pin "2") (pinfunction "2_2") (pintype "passive"))
      (node (ref "L1") (pin "1") (pinfunction "1_1") (pintype "passive"))
      (node (ref "U1") (pin "2") (pinfunction "SW_2") (pintype "passive"))
    )
    (net (code "75") (name "Net-(U3-V33O)") (class "Default")
      (node (ref "C11") (pin "1") (pinfunction "1_1") (pintype "passive"))
      (node (ref "U3") (pin "8") (pinfunction "V33O_8") (pintype "passive"))
    )
    (net (code "76") (name "Net-(U4A-OSC_IN)") (class "Default")
      (node (ref "C26") (pin "2") (pinfunction "2_2") (pintype "passive"))
      (node (ref "U4") (pin "5") (pinfunction "OSC_IN_5") (pintype "bidirectional"))
      (node (ref "Xtal1") (pin "1") (pinfunction "1_1") (pintype "passive"))
    )
    (net (code "77") (name "Net-(U4A-OSC_OUT)") (class "Default")
      (node (ref "C27") (pin "2") (pinfunction "2_2") (pintype "passive"))
      (node (ref "U4") (pin "6") (pinfunction "OSC_OUT_6") (pintype "bidirectional"))
      (node (ref "Xtal1") (pin "3") (pinfunction "3_3") (pintype "passive"))
    )
    (net (code "78") (name "Net-(U5-CS)") (class "Default")
      (node (ref "R24") (pin "2") (pinfunction "2_2") (pintype "passive"))
      (node (ref "U5") (pin "10") (pinfunction "CS_10") (pintype "passive"))
    )
    (net (code "79") (name "Net-(U5-IS)") (class "Default")
      (node (ref "R28") (pin "2") (pinfunction "2_2") (pintype "passive"))
      (node (ref "U5") (pin "13") (pinfunction "IS_13") (pintype "passive"))
    )
    (net (code "80") (name "Net-(U5-SCLK)") (class "Default")
      (node (ref "R26") (pin "2") (pinfunction "2_2") (pintype "passive"))
      (node (ref "U5") (pin "6") (pinfunction "SCLK_6") (pintype "passive"))
    )
    (net (code "81") (name "Net-(U5-SDI)") (class "Default")
      (node (ref "R23") (pin "2") (pinfunction "2_2") (pintype "passive"))
      (node (ref "U5") (pin "2") (pinfunction "SDI_2") (pintype "passive"))
    )
    (net (code "82") (name "Net-(U5-SDO)") (class "Default")
      (node (ref "R22") (pin "1") (pinfunction "1_1") (pintype "passive"))
      (node (ref "U5") (pin "9") (pinfunction "SDO_9") (pintype "passive"))
      (node (ref "U6") (pin "2") (pinfunction "SDI_2") (pintype "passive"))
    )
    (net (code "83") (name "Net-(U6-CS)") (class "Default")
      (node (ref "R25") (pin "2") (pinfunction "2_2") (pintype "passive"))
      (node (ref "U6") (pin "10") (pinfunction "CS_10") (pintype "passive"))
    )
    (net (code "84") (name "Net-(U6-IS)") (class "Default")
      (node (ref "R29") (pin "2") (pinfunction "2_2") (pintype "passive"))
      (node (ref "U6") (pin "13") (pinfunction "IS_13") (pintype "passive"))
    )
    (net (code "85") (name "Net-(U6-SCLK)") (class "Default")
      (node (ref "R27") (pin "2") (pinfunction "2_2") (pintype "passive"))
      (node (ref "U6") (pin "6") (pinfunction "SCLK_6") (pintype "passive"))
    )
    (net (code "86") (name "OLED_3V3") (class "Default")
      (node (ref "C35") (pin "1") (pinfunction "1_1") (pintype "passive"))
      (node (ref "P1") (pin "2") (pinfunction "2_2") (pintype "passive"))
      (node (ref "SW3") (pin "3") (pinfunction "3_3") (pintype "passive"))
    )
    (net (code "87") (name "RF_5V") (class "Default")
      (node (ref "C31") (pin "1") (pinfunction "1_1") (pintype "passive"))
      (node (ref "P5") (pin "3") (pinfunction "3_3") (pintype "passive"))
      (node (ref "SW3") (pin "2") (pinfunction "2_2") (pintype "passive"))
    )
    (net (code "88") (name "SW_5V") (class "Default")
      (node (ref "C1") (pin "2") (pinfunction "2_2") (pintype "passive"))
      (node (ref "C8") (pin "2") (pinfunction "2_2") (pintype "passive"))
      (node (ref "C9") (pin "2") (pinfunction "2_2") (pintype "passive"))
      (node (ref "L1") (pin "2") (pinfunction "2_2") (pintype "passive"))
      (node (ref "R1") (pin "2") (pinfunction "2_2") (pintype "passive"))
      (node (ref "SW2") (pin "3") (pinfunction "3_3") (pintype "passive"))
      (node (ref "SW2") (pin "4") (pinfunction "4_4") (pintype "passive"))
    )
    (net (code "89") (name "USB_5V") (class "Default")
      (node (ref "D1") (pin "1") (pinfunction "C_1") (pintype "passive"))
      (node (ref "J2") (pin "A4") (pinfunction "VBUS_A4") (pintype "power_in"))
      (node (ref "J2") (pin "A9") (pinfunction "VBUS_A9") (pintype "power_in"))
      (node (ref "J2") (pin "B4") (pinfunction "VBUS_B4") (pintype "power_in"))
      (node (ref "J2") (pin "B9") (pinfunction "VBUS_B9") (pintype "power_in"))
      (node (ref "SW2") (pin "1") (pinfunction "1_1") (pintype "passive"))
      (node (ref "SW2") (pin "6") (pinfunction "6_6") (pintype "passive"))
      (node (ref "U3") (pin "7") (pinfunction "VDD_7") (pintype "passive"))
    )
    (net (code "90") (name "unconnected-(J2-SBU1-PadA8)") (class "Default")
      (node (ref "J2") (pin "A8") (pinfunction "SBU1_A8") (pintype "bidirectional+no_connect"))
    )
    (net (code "91") (name "unconnected-(J2-SBU2-PadB8)") (class "Default")
      (node (ref "J2") (pin "B8") (pinfunction "SBU2_B8") (pintype "bidirectional+no_connect"))
    )
    (net (code "92") (name "unconnected-(J5-Pad5)") (class "Default")
      (node (ref "J5") (pin "5") (pinfunction "5_5") (pintype "passive+no_connect"))
    )
    (net (code "93") (name "unconnected-(J6-Pad5)") (class "Default")
      (node (ref "J6") (pin "5") (pinfunction "5_5") (pintype "passive+no_connect"))
    )
    (net (code "94") (name "unconnected-(J7-Pad5)") (class "Default")
      (node (ref "J7") (pin "5") (pinfunction "5_5") (pintype "passive+no_connect"))
    )
    (net (code "95") (name "unconnected-(U4A-JTDI-Pad38)") (class "Default")
      (node (ref "U4") (pin "38") (pinfunction "JTDI_38") (pintype "bidirectional+no_connect"))
    )
    (net (code "96") (name "unconnected-(U4A-PA1-Pad11)") (class "Default")
      (node (ref "U4") (pin "11") (pinfunction "PA1_11") (pintype "bidirectional+no_connect"))
    )
    (net (code "97") (name "unconnected-(U4A-PA2-Pad12)") (class "Default")
      (node (ref "U4") (pin "12") (pinfunction "PA2_12") (pintype "bidirectional+no_connect"))
    )
    (net (code "98") (name "unconnected-(U4A-PA4-Pad14)") (class "Default")
      (node (ref "U4") (pin "14") (pinfunction "PA4_14") (pintype "bidirectional"))
    )
    (net (code "99") (name "unconnected-(U4A-PA8-Pad29)") (class "Default")
      (node (ref "U4") (pin "29") (pinfunction "PA8_29") (pintype "bidirectional+no_connect"))
    )
    (net (code "100") (name "unconnected-(U4A-PB2_{slash}_BOOT1-Pad20)") (class "Default")
      (node (ref "U4") (pin "20") (pinfunction "PB2_/_BOOT1_20") (pintype "bidirectional+no_connect"))
    )
    (net (code "101") (name "unconnected-(U4A-PB12-Pad25)") (class "Default")
      (node (ref "U4") (pin "25") (pinfunction "PB12_25") (pintype "bidirectional"))
    )
    (net (code "102") (name "unconnected-(U4A-PB14-Pad27)") (class "Default")
      (node (ref "U4") (pin "27") (pinfunction "PB14_27") (pintype "bidirectional+no_connect"))
    )
    (net (code "103") (name "unconnected-(U4A-PB15-Pad28)") (class "Default")
      (node (ref "U4") (pin "28") (pinfunction "PB15_28") (pintype "bidirectional+no_connect"))
    )
  )
)
